# MIXR_Input_System_-_Power_Control.net
KiCad netlist of a schematic drawn in Altium Designer
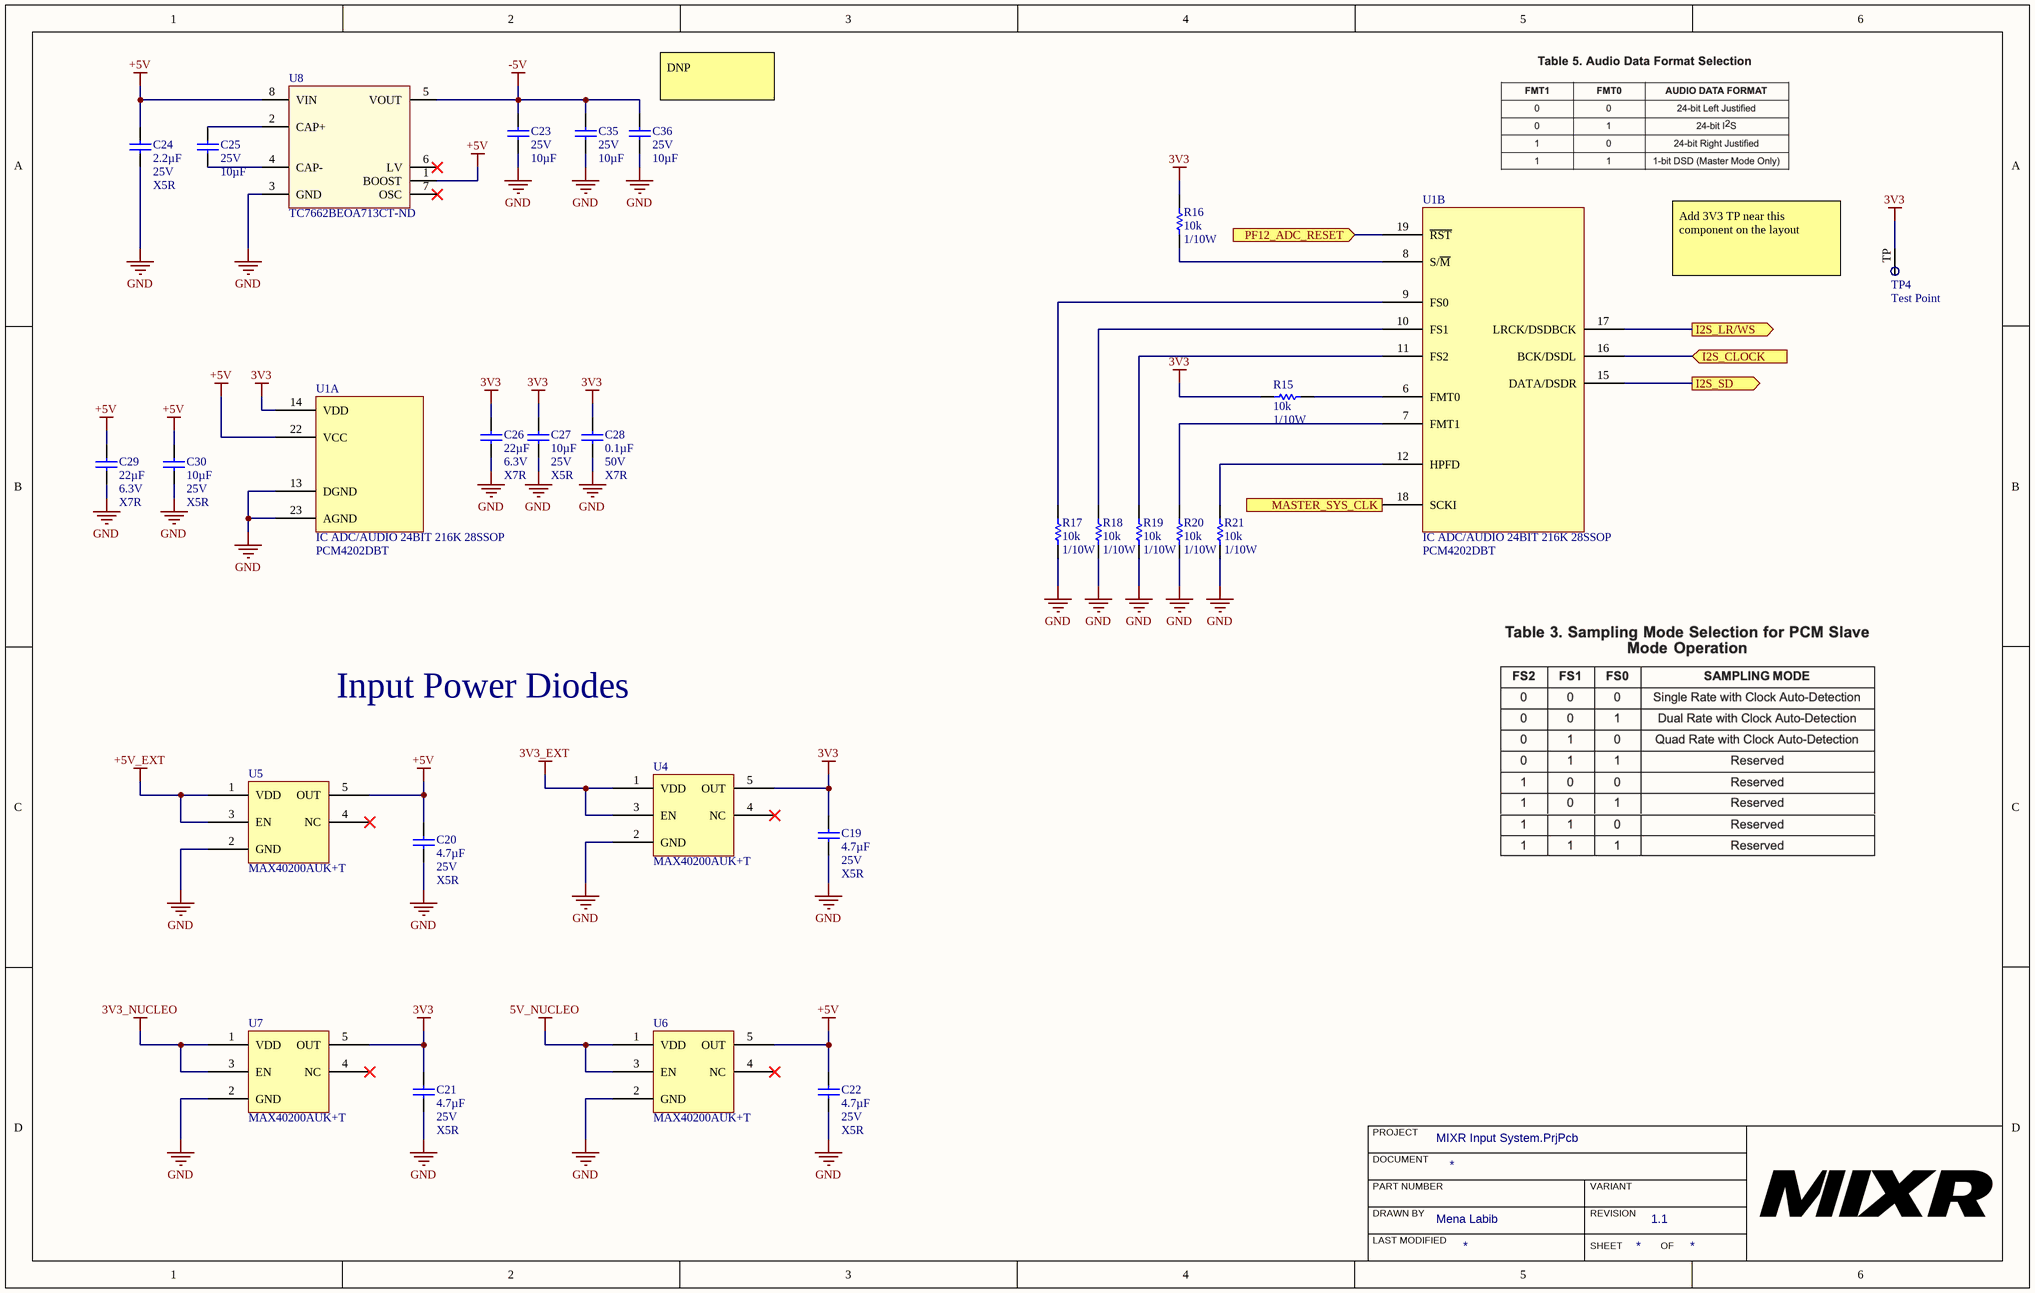
[diagram p0: MIXR Input System - Power&Control.SchDoc]

(export (version "E")
  (design (tool "Eeschema 10.0.6"))
  (components
    (comp (ref "C19")
      (value "CAP CER 4.7UF 25V 10% X5R 0603")
      (footprint "CAP, 0603")
      (description "4.7µF ±10% 25V Ceramic Capacitor X5R 0603 (1608 Metric)")
      (fields
        (field (name "TOLERANCE") "±10%")
        (field (name "CAPACITANCE") "4.7µF")
        (field (name "VOLTAGE") "25V")
        (field (name "TEMPERATURE COEFFICIENT") "X5R")
      )
      (libsource (lib "Schematic Diagrams") (part "CAP CER 4.7UF 25V 10% X5R 0603"))
    )
    (comp (ref "C20")
      (value "CAP CER 4.7UF 25V 10% X5R 0603")
      (footprint "CAP, 0603")
      (description "4.7µF ±10% 25V Ceramic Capacitor X5R 0603 (1608 Metric)")
      (fields
        (field (name "TOLERANCE") "±10%")
        (field (name "CAPACITANCE") "4.7µF")
        (field (name "VOLTAGE") "25V")
        (field (name "TEMPERATURE COEFFICIENT") "X5R")
      )
      (libsource (lib "Schematic Diagrams") (part "CAP CER 4.7UF 25V 10% X5R 0603"))
    )
    (comp (ref "C21")
      (value "CAP CER 4.7UF 25V 10% X5R 0603")
      (footprint "CAP, 0603")
      (description "4.7µF ±10% 25V Ceramic Capacitor X5R 0603 (1608 Metric)")
      (fields
        (field (name "TOLERANCE") "±10%")
        (field (name "CAPACITANCE") "4.7µF")
        (field (name "VOLTAGE") "25V")
        (field (name "TEMPERATURE COEFFICIENT") "X5R")
      )
      (libsource (lib "Schematic Diagrams") (part "CAP CER 4.7UF 25V 10% X5R 0603"))
    )
    (comp (ref "C22")
      (value "CAP CER 4.7UF 25V 10% X5R 0603")
      (footprint "CAP, 0603")
      (description "4.7µF ±10% 25V Ceramic Capacitor X5R 0603 (1608 Metric)")
      (fields
        (field (name "TOLERANCE") "±10%")
        (field (name "CAPACITANCE") "4.7µF")
        (field (name "VOLTAGE") "25V")
        (field (name "TEMPERATURE COEFFICIENT") "X5R")
      )
      (libsource (lib "Schematic Diagrams") (part "CAP CER 4.7UF 25V 10% X5R 0603"))
    )
    (comp (ref "C23")
      (value "CAP CER 10uF 25V 10% X5R 0805")
      (footprint "CAP, 0805")
      (description "10µF ±10% 25V Ceramic Capacitor X5R 0805 (2012 Metric)")
      (fields
        (field (name "MANUFACTURER") "Murata Electronics North America")
        (field (name "MANUFACTURER PART NUMBER") "GRM21BR61E106KA73L")
        (field (name "VOLTAGE - RATED") "25V")
        (field (name "CAPACITANCE") "10µF")
      )
      (libsource (lib "Schematic Diagrams") (part "CAP CER 10uF 25V 10% X5R 0805"))
    )
    (comp (ref "C24")
      (value "CAP CER 2.2UF 25V 10% X5R 0603")
      (footprint "CAP, 0603")
      (description "2.2µF ±10% 25V Ceramic Capacitor X5R 0603 (1608 Metric)")
      (fields
        (field (name "TOLERANCE") "±10%")
        (field (name "CAPACITANCE") "2.2µF")
        (field (name "VOLTAGE") "25V")
        (field (name "TEMPERATURE COEFFICIENT") "X5R")
      )
      (libsource (lib "Schematic Diagrams") (part "CAP CER 2.2UF 25V 10% X5R 0603"))
    )
    (comp (ref "C25")
      (value "CAP CER 10uF 25V 10% X5R 0805")
      (footprint "CAP, 0805")
      (description "10µF ±10% 25V Ceramic Capacitor X5R 0805 (2012 Metric)")
      (fields
        (field (name "MANUFACTURER") "Murata Electronics North America")
        (field (name "MANUFACTURER PART NUMBER") "GRM21BR61E106KA73L")
        (field (name "VOLTAGE - RATED") "25V")
        (field (name "CAPACITANCE") "10µF")
      )
      (libsource (lib "Schematic Diagrams") (part "CAP CER 10uF 25V 10% X5R 0805"))
    )
    (comp (ref "C26")
      (value "CAP CER 22UF 6.3V ±10% X7R 1206")
      (footprint "CAP, 1206")
      (description "22µF ±10% 6.3V Ceramic Capacitor X7R 1206 (3216 Metric)")
      (fields
        (field (name "TOLERANCE") "±10%")
        (field (name "CAPACITANCE") "22µF")
        (field (name "VOLTAGE") "6.3V")
        (field (name "TEMPERATURE COEFFICIENT") "X7R")
      )
      (libsource (lib "Schematic Diagrams") (part "CAP CER 22UF 6.3V ±10% X7R 1206"))
    )
    (comp (ref "C27")
      (value "CAP CER 10uF 25V 20% X5R 0603")
      (footprint "CAP, 0603")
      (description "10µF ±20% 25V Ceramic Capacitor X5R 0603 (1608 Metric)")
      (fields
        (field (name "TOLERANCE") "±20%")
        (field (name "CAPACITANCE") "10µF")
        (field (name "VOLTAGE") "25V")
        (field (name "TEMPERATURE COEFFICIENT") "X5R")
      )
      (libsource (lib "Schematic Diagrams") (part "CAP CER 10uF 25V 20% X5R 0603"))
    )
    (comp (ref "C28")
      (value "CAP CER 0.1UF 50V 10% X7R 0603")
      (footprint "CAP, 0603")
      (description "0.10µF ±10% 50V Ceramic Capacitor X7R 0603 (1608 Metric)")
      (fields
        (field (name "TOLERANCE") "±10%")
        (field (name "CAPACITANCE") "0.1µF")
        (field (name "VOLTAGE") "50V")
        (field (name "TEMPERATURE COEFFICIENT") "X7R")
      )
      (libsource (lib "Schematic Diagrams") (part "CAP CER 0.1UF 50V 10% X7R 0603"))
    )
    (comp (ref "C29")
      (value "CAP CER 22UF 6.3V ±10% X7R 1206")
      (footprint "CAP, 1206")
      (description "22µF ±10% 6.3V Ceramic Capacitor X7R 1206 (3216 Metric)")
      (fields
        (field (name "TOLERANCE") "±10%")
        (field (name "CAPACITANCE") "22µF")
        (field (name "VOLTAGE") "6.3V")
        (field (name "TEMPERATURE COEFFICIENT") "X7R")
      )
      (libsource (lib "Schematic Diagrams") (part "CAP CER 22UF 6.3V ±10% X7R 1206"))
    )
    (comp (ref "C30")
      (value "CAP CER 10uF 25V 20% X5R 0603")
      (footprint "CAP, 0603")
      (description "10µF ±20% 25V Ceramic Capacitor X5R 0603 (1608 Metric)")
      (fields
        (field (name "TOLERANCE") "±20%")
        (field (name "CAPACITANCE") "10µF")
        (field (name "VOLTAGE") "25V")
        (field (name "TEMPERATURE COEFFICIENT") "X5R")
      )
      (libsource (lib "Schematic Diagrams") (part "CAP CER 10uF 25V 20% X5R 0603"))
    )
    (comp (ref "C35")
      (value "CAP CER 10uF 25V 10% X5R 0805")
      (footprint "CAP, 0805")
      (description "10µF ±10% 25V Ceramic Capacitor X5R 0805 (2012 Metric)")
      (fields
        (field (name "MANUFACTURER") "Murata Electronics North America")
        (field (name "MANUFACTURER PART NUMBER") "GRM21BR61E106KA73L")
        (field (name "VOLTAGE - RATED") "25V")
        (field (name "CAPACITANCE") "10µF")
      )
      (libsource (lib "Schematic Diagrams") (part "CAP CER 10uF 25V 10% X5R 0805"))
    )
    (comp (ref "C36")
      (value "CAP CER 10uF 25V 10% X5R 0805")
      (footprint "CAP, 0805")
      (description "10µF ±10% 25V Ceramic Capacitor X5R 0805 (2012 Metric)")
      (fields
        (field (name "MANUFACTURER") "Murata Electronics North America")
        (field (name "MANUFACTURER PART NUMBER") "GRM21BR61E106KA73L")
        (field (name "VOLTAGE - RATED") "25V")
        (field (name "CAPACITANCE") "10µF")
      )
      (libsource (lib "Schematic Diagrams") (part "CAP CER 10uF 25V 10% X5R 0805"))
    )
    (comp (ref "R15")
      (value "RES 10K OHM 1% 1/10W 0603")
      (footprint "RES, 0603")
      (description "RES SMD 10K OHM 1% 1/10W 0603")
      (fields
        (field (name "TOLERANCE") "±1%")
        (field (name "RESISTANCE") "10k")
        (field (name "POWER") "1/10W")
      )
      (libsource (lib "Schematic Diagrams") (part "RES 10K OHM 1% 1/10W 0603"))
    )
    (comp (ref "R16")
      (value "RES 10K OHM 1% 1/10W 0603")
      (footprint "RES, 0603")
      (description "RES SMD 10K OHM 1% 1/10W 0603")
      (fields
        (field (name "TOLERANCE") "±1%")
        (field (name "RESISTANCE") "10k")
        (field (name "POWER") "1/10W")
      )
      (libsource (lib "Schematic Diagrams") (part "RES 10K OHM 1% 1/10W 0603"))
    )
    (comp (ref "R17")
      (value "RES 10K OHM 1% 1/10W 0603")
      (footprint "RES, 0603")
      (description "RES SMD 10K OHM 1% 1/10W 0603")
      (fields
        (field (name "TOLERANCE") "±1%")
        (field (name "RESISTANCE") "10k")
        (field (name "POWER") "1/10W")
      )
      (libsource (lib "Schematic Diagrams") (part "RES 10K OHM 1% 1/10W 0603"))
    )
    (comp (ref "R18")
      (value "RES 10K OHM 1% 1/10W 0603")
      (footprint "RES, 0603")
      (description "RES SMD 10K OHM 1% 1/10W 0603")
      (fields
        (field (name "TOLERANCE") "±1%")
        (field (name "RESISTANCE") "10k")
        (field (name "POWER") "1/10W")
      )
      (libsource (lib "Schematic Diagrams") (part "RES 10K OHM 1% 1/10W 0603"))
    )
    (comp (ref "R19")
      (value "RES 10K OHM 1% 1/10W 0603")
      (footprint "RES, 0603")
      (description "RES SMD 10K OHM 1% 1/10W 0603")
      (fields
        (field (name "TOLERANCE") "±1%")
        (field (name "RESISTANCE") "10k")
        (field (name "POWER") "1/10W")
      )
      (libsource (lib "Schematic Diagrams") (part "RES 10K OHM 1% 1/10W 0603"))
    )
    (comp (ref "R20")
      (value "RES 10K OHM 1% 1/10W 0603")
      (footprint "RES, 0603")
      (description "RES SMD 10K OHM 1% 1/10W 0603")
      (fields
        (field (name "TOLERANCE") "±1%")
        (field (name "RESISTANCE") "10k")
        (field (name "POWER") "1/10W")
      )
      (libsource (lib "Schematic Diagrams") (part "RES 10K OHM 1% 1/10W 0603"))
    )
    (comp (ref "R21")
      (value "RES 10K OHM 1% 1/10W 0603")
      (footprint "RES, 0603")
      (description "RES SMD 10K OHM 1% 1/10W 0603")
      (fields
        (field (name "TOLERANCE") "±1%")
        (field (name "RESISTANCE") "10k")
        (field (name "POWER") "1/10W")
      )
      (libsource (lib "Schematic Diagrams") (part "RES 10K OHM 1% 1/10W 0603"))
    )
    (comp (ref "TP4")
      (value "Test Point")
      (footprint "Test Point")
      (libsource (lib "Schematic Diagrams") (part "Test Point"))
    )
    (comp (ref "U1")
      (value "IC ADC/AUDIO 24BIT 216K 28SSOP")
      (footprint "IC ADC 24 BIT AUDIO 216 KHZ SSOP-28")
      (description "ADC, Audio 24 bit 216k DSP, PCM 28-SSOP")
      (fields
        (field (name "MANUFACTURER") "Texas Instruments")
        (field (name "MANUFACTURER PART NUMBER") "PCM4202DBT")
      )
      (libsource (lib "Schematic Diagrams") (part "IC ADC 24 BIT AUDIO 216KHZ SSOP-28"))
    )
    (comp (ref "U4")
      (value "IC IDEAL DIODE CURRENT SWITCH SOT23-5")
      (footprint "SOT95P280X145-5N")
      (description "OR Controller Source Selector Switch P-Channel 1:1 SOT-23-5")
      (fields (field (name "MANUFACTURER") "Maxim") (field (name "MANUFACTURER PART NUMBER") "MAX40200AUK+T"))
      (libsource (lib "Schematic Diagrams") (part "IC IDEAL DIODE CURRENT SWITCH SOT23-5"))
    )
    (comp (ref "U5")
      (value "IC IDEAL DIODE CURRENT SWITCH SOT23-5")
      (footprint "SOT95P280X145-5N")
      (description "OR Controller Source Selector Switch P-Channel 1:1 SOT-23-5")
      (fields (field (name "MANUFACTURER") "Maxim") (field (name "MANUFACTURER PART NUMBER") "MAX40200AUK+T"))
      (libsource (lib "Schematic Diagrams") (part "IC IDEAL DIODE CURRENT SWITCH SOT23-5"))
    )
    (comp (ref "U6")
      (value "IC IDEAL DIODE CURRENT SWITCH SOT23-5")
      (footprint "SOT95P280X145-5N")
      (description "OR Controller Source Selector Switch P-Channel 1:1 SOT-23-5")
      (fields (field (name "MANUFACTURER") "Maxim") (field (name "MANUFACTURER PART NUMBER") "MAX40200AUK+T"))
      (libsource (lib "Schematic Diagrams") (part "IC IDEAL DIODE CURRENT SWITCH SOT23-5"))
    )
    (comp (ref "U7")
      (value "IC IDEAL DIODE CURRENT SWITCH SOT23-5")
      (footprint "SOT95P280X145-5N")
      (description "OR Controller Source Selector Switch P-Channel 1:1 SOT-23-5")
      (fields (field (name "MANUFACTURER") "Maxim") (field (name "MANUFACTURER PART NUMBER") "MAX40200AUK+T"))
      (libsource (lib "Schematic Diagrams") (part "IC IDEAL DIODE CURRENT SWITCH SOT23-5"))
    )
    (comp (ref "U8")
      (value "IC REG SWTCHD CAP INV 20MA 8SOIC")
      (fields
        (field (name "MANUFACTURER") "Microchip")
        (field (name "MANUFACTURER PART NUMBER") "TC7662BEOA713")
        (field (name "SUPPLIER PART NUMBER 1") "TC7662BEOA713CT-ND")
      )
      (libsource (lib "Schematic Diagrams") (part "IC REG SWTCHD CAP INV 20MA 8SOIC"))
    )
  )
  (nets
    (net (code "1") (name "+5V") (class "Default")
      (node (ref "C20") (pin "1") (pinfunction "1_1") (pintype "passive"))
      (node (ref "C22") (pin "1") (pinfunction "1_1") (pintype "passive"))
      (node (ref "C24") (pin "2") (pinfunction "2_2") (pintype "passive"))
      (node (ref "C29") (pin "1") (pinfunction "1_1") (pintype "passive"))
      (node (ref "C30") (pin "1") (pinfunction "1_1") (pintype "passive"))
      (node (ref "U1") (pin "22") (pinfunction "VCC_22") (pintype "passive"))
      (node (ref "U5") (pin "5") (pinfunction "OUT_5") (pintype "passive"))
      (node (ref "U6") (pin "5") (pinfunction "OUT_5") (pintype "passive"))
      (node (ref "U8") (pin "1") (pinfunction "BOOST_1") (pintype "power_in"))
      (node (ref "U8") (pin "8") (pinfunction "VIN_8") (pintype "power_in"))
    )
    (net (code "2") (name "+5V_EXT") (class "Default")
      (node (ref "U5") (pin "1") (pinfunction "VDD_1") (pintype "passive"))
      (node (ref "U5") (pin "3") (pinfunction "EN_3") (pintype "passive"))
    )
    (net (code "3") (name "-5V") (class "Default")
      (node (ref "C23") (pin "1") (pinfunction "1_1") (pintype "passive"))
      (node (ref "C35") (pin "1") (pinfunction "1_1") (pintype "passive"))
      (node (ref "C36") (pin "1") (pinfunction "1_1") (pintype "passive"))
      (node (ref "U8") (pin "5") (pinfunction "VOUT_5") (pintype "power_in"))
    )
    (net (code "4") (name "/I2S_CLOCK") (class "Default")
      (node (ref "U1") (pin "16") (pinfunction "BCK/DSDL_16") (pintype "passive"))
    )
    (net (code "5") (name "/I2S_LR{slash}WS") (class "Default")
      (node (ref "U1") (pin "17") (pinfunction "LRCK/DSDBCK_17") (pintype "passive"))
    )
    (net (code "6") (name "/I2S_SD") (class "Default")
      (node (ref "U1") (pin "15") (pinfunction "DATA/DSDR_15") (pintype "passive"))
    )
    (net (code "7") (name "/MASTER_SYS_CLK") (class "Default")
      (node (ref "U1") (pin "18") (pinfunction "SCKI_18") (pintype "passive"))
    )
    (net (code "8") (name "/PF12_ADC_RESET") (class "Default")
      (node (ref "U1") (pin "19") (pinfunction "~{RST}_19") (pintype "passive"))
    )
    (net (code "9") (name "3V3") (class "Default")
      (node (ref "C19") (pin "1") (pinfunction "1_1") (pintype "passive"))
      (node (ref "C21") (pin "1") (pinfunction "1_1") (pintype "passive"))
      (node (ref "C26") (pin "1") (pinfunction "1_1") (pintype "passive"))
      (node (ref "C27") (pin "1") (pinfunction "1_1") (pintype "passive"))
      (node (ref "C28") (pin "1") (pinfunction "1_1") (pintype "passive"))
      (node (ref "R15") (pin "1") (pinfunction "1_1") (pintype "passive"))
      (node (ref "R16") (pin "1") (pinfunction "1_1") (pintype "passive"))
      (node (ref "TP4") (pin "TP") (pinfunction "1_TP") (pintype "passive"))
      (node (ref "U1") (pin "14") (pinfunction "VDD_14") (pintype "passive"))
      (node (ref "U4") (pin "5") (pinfunction "OUT_5") (pintype "passive"))
      (node (ref "U7") (pin "5") (pinfunction "OUT_5") (pintype "passive"))
    )
    (net (code "10") (name "3V3_EXT") (class "Default")
      (node (ref "U4") (pin "1") (pinfunction "VDD_1") (pintype "passive"))
      (node (ref "U4") (pin "3") (pinfunction "EN_3") (pintype "passive"))
    )
    (net (code "11") (name "3V3_NUCLEO") (class "Default")
      (node (ref "U7") (pin "1") (pinfunction "VDD_1") (pintype "passive"))
      (node (ref "U7") (pin "3") (pinfunction "EN_3") (pintype "passive"))
    )
    (net (code "12") (name "5V_NUCLEO") (class "Default")
      (node (ref "U6") (pin "1") (pinfunction "VDD_1") (pintype "passive"))
      (node (ref "U6") (pin "3") (pinfunction "EN_3") (pintype "passive"))
    )
    (net (code "13") (name "GND") (class "Default")
      (node (ref "C19") (pin "2") (pinfunction "2_2") (pintype "passive"))
      (node (ref "C20") (pin "2") (pinfunction "2_2") (pintype "passive"))
      (node (ref "C21") (pin "2") (pinfunction "2_2") (pintype "passive"))
      (node (ref "C22") (pin "2") (pinfunction "2_2") (pintype "passive"))
      (node (ref "C23") (pin "2") (pinfunction "2_2") (pintype "passive"))
      (node (ref "C24") (pin "1") (pinfunction "1_1") (pintype "passive"))
      (node (ref "C26") (pin "2") (pinfunction "2_2") (pintype "passive"))
      (node (ref "C27") (pin "2") (pinfunction "2_2") (pintype "passive"))
      (node (ref "C28") (pin "2") (pinfunction "2_2") (pintype "passive"))
      (node (ref "C29") (pin "2") (pinfunction "2_2") (pintype "passive"))
      (node (ref "C30") (pin "2") (pinfunction "2_2") (pintype "passive"))
      (node (ref "C35") (pin "2") (pinfunction "2_2") (pintype "passive"))
      (node (ref "C36") (pin "2") (pinfunction "2_2") (pintype "passive"))
      (node (ref "R17") (pin "2") (pinfunction "2_2") (pintype "passive"))
      (node (ref "R18") (pin "2") (pinfunction "2_2") (pintype "passive"))
      (node (ref "R19") (pin "2") (pinfunction "2_2") (pintype "passive"))
      (node (ref "R20") (pin "2") (pinfunction "2_2") (pintype "passive"))
      (node (ref "R21") (pin "2") (pinfunction "2_2") (pintype "passive"))
      (node (ref "U1") (pin "13") (pinfunction "DGND_13") (pintype "passive"))
      (node (ref "U1") (pin "23") (pinfunction "AGND_23") (pintype "passive"))
      (node (ref "U4") (pin "2") (pinfunction "GND_2") (pintype "passive"))
      (node (ref "U5") (pin "2") (pinfunction "GND_2") (pintype "passive"))
      (node (ref "U6") (pin "2") (pinfunction "GND_2") (pintype "passive"))
      (node (ref "U7") (pin "2") (pinfunction "GND_2") (pintype "passive"))
      (node (ref "U8") (pin "3") (pinfunction "GND_3") (pintype "power_in"))
    )
    (net (code "14") (name "Net-(U1B-FMT0)") (class "Default")
      (node (ref "R15") (pin "2") (pinfunction "2_2") (pintype "passive"))
      (node (ref "U1") (pin "6") (pinfunction "FMT0_6") (pintype "passive"))
    )
    (net (code "15") (name "Net-(U1B-FMT1)") (class "Default")
      (node (ref "R20") (pin "1") (pinfunction "1_1") (pintype "passive"))
      (node (ref "U1") (pin "7") (pinfunction "FMT1_7") (pintype "passive"))
    )
    (net (code "16") (name "Net-(U1B-FS0)") (class "Default")
      (node (ref "R17") (pin "1") (pinfunction "1_1") (pintype "passive"))
      (node (ref "U1") (pin "9") (pinfunction "FS0_9") (pintype "passive"))
    )
    (net (code "17") (name "Net-(U1B-FS1)") (class "Default")
      (node (ref "R18") (pin "1") (pinfunction "1_1") (pintype "passive"))
      (node (ref "U1") (pin "10") (pinfunction "FS1_10") (pintype "passive"))
    )
    (net (code "18") (name "Net-(U1B-FS2)") (class "Default")
      (node (ref "R19") (pin "1") (pinfunction "1_1") (pintype "passive"))
      (node (ref "U1") (pin "11") (pinfunction "FS2_11") (pintype "passive"))
    )
    (net (code "19") (name "Net-(U1B-HPFD)") (class "Default")
      (node (ref "R21") (pin "1") (pinfunction "1_1") (pintype "passive"))
      (node (ref "U1") (pin "12") (pinfunction "HPFD_12") (pintype "passive"))
    )
    (net (code "20") (name "Net-(U1B-S{slash}~{M})") (class "Default")
      (node (ref "R16") (pin "2") (pinfunction "2_2") (pintype "passive"))
      (node (ref "U1") (pin "8") (pinfunction "S/~{M}_8") (pintype "passive"))
    )
    (net (code "21") (name "Net-(U8-CAP+)") (class "Default")
      (node (ref "C25") (pin "1") (pinfunction "1_1") (pintype "passive"))
      (node (ref "U8") (pin "2") (pinfunction "CAP+_2") (pintype "passive"))
    )
    (net (code "22") (name "Net-(U8-CAP-)") (class "Default")
      (node (ref "C25") (pin "2") (pinfunction "2_2") (pintype "passive"))
      (node (ref "U8") (pin "4") (pinfunction "CAP-_4") (pintype "power_in"))
    )
    (net (code "23") (name "unconnected-(U4-NC-Pad4)") (class "Default")
      (node (ref "U4") (pin "4") (pinfunction "NC_4") (pintype "passive+no_connect"))
    )
    (net (code "24") (name "unconnected-(U5-NC-Pad4)") (class "Default")
      (node (ref "U5") (pin "4") (pinfunction "NC_4") (pintype "passive+no_connect"))
    )
    (net (code "25") (name "unconnected-(U6-NC-Pad4)") (class "Default")
      (node (ref "U6") (pin "4") (pinfunction "NC_4") (pintype "passive+no_connect"))
    )
    (net (code "26") (name "unconnected-(U7-NC-Pad4)") (class "Default")
      (node (ref "U7") (pin "4") (pinfunction "NC_4") (pintype "passive+no_connect"))
    )
    (net (code "27") (name "unconnected-(U8-LV-Pad6)") (class "Default")
      (node (ref "U8") (pin "6") (pinfunction "LV_6") (pintype "power_in+no_connect"))
    )
    (net (code "28") (name "unconnected-(U8-OSC-Pad7)") (class "Default")
      (node (ref "U8") (pin "7") (pinfunction "OSC_7") (pintype "power_in+no_connect"))
    )
  )
)
